# temperature_sensor.net
KiCad netlist of a schematic drawn in EAGLE
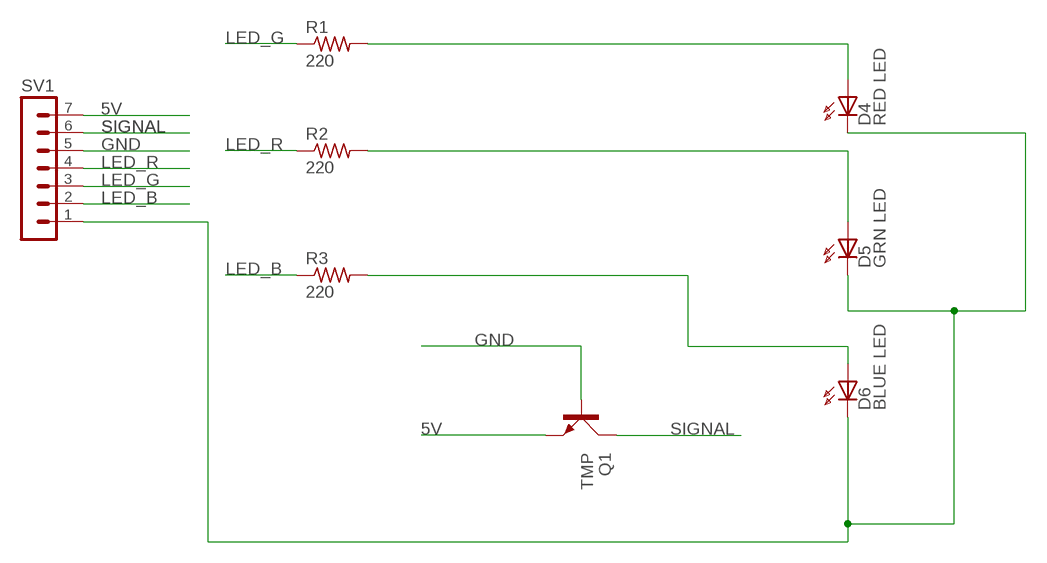
[diagram p0: schematic, sheet 1]

(export (version "E")
  (design (tool "Eeschema 10.0.6"))
  (components
    (comp (ref "D4")
      (value "RED LED")
      (footprint "eagle-import:HLMP6")
      (fields (field (name "MF") "AGILENT TECHNOLOGIES") (field (name "MPN") "HLMP-6500"))
      (libsource (lib "eagle-import") (part "HLMP6"))
    )
    (comp (ref "D5")
      (value "GRN LED")
      (footprint "eagle-import:HLMP6")
      (fields (field (name "MF") "AGILENT TECHNOLOGIES") (field (name "MPN") "HLMP-6500"))
      (libsource (lib "eagle-import") (part "HLMP6"))
    )
    (comp (ref "D6")
      (value "BLUE LED")
      (footprint "eagle-import:HLMP6")
      (fields (field (name "MF") "AGILENT TECHNOLOGIES") (field (name "MPN") "HLMP-6500"))
      (libsource (lib "eagle-import") (part "HLMP6"))
    )
    (comp (ref "Q1")
      (value "TMP")
      (footprint "eagle-import:TO126AV")
      (libsource (lib "eagle-import") (part "BD139"))
    )
    (comp (ref "R1")
      (value "220")
      (footprint "eagle-import:R1206")
      (libsource (lib "eagle-import") (part "R-US_R1206"))
    )
    (comp (ref "R2")
      (value "220")
      (footprint "eagle-import:R1206")
      (libsource (lib "eagle-import") (part "R-US_R1206"))
    )
    (comp (ref "R3")
      (value "220")
      (footprint "eagle-import:R1206")
      (libsource (lib "eagle-import") (part "R-US_R1206"))
    )
    (comp (ref "SV1")
      (value "MA07-1")
      (footprint "eagle-import:MA07-1")
      (libsource (lib "eagle-import") (part "MA07-1"))
    )
  )
  (nets
    (net (code "1") (name "/5V") (class "Default")
      (node (ref "Q1") (pin "E") (pinfunction "E_E") (pintype "passive"))
      (node (ref "SV1") (pin "7") (pinfunction "7_7") (pintype "passive"))
    )
    (net (code "2") (name "/GND") (class "Default")
      (node (ref "Q1") (pin "B") (pinfunction "B_B") (pintype "passive"))
      (node (ref "SV1") (pin "5") (pinfunction "5_5") (pintype "passive"))
    )
    (net (code "3") (name "/LED_B") (class "Default")
      (node (ref "R3") (pin "1") (pinfunction "1_1") (pintype "passive"))
      (node (ref "SV1") (pin "2") (pinfunction "2_2") (pintype "passive"))
    )
    (net (code "4") (name "/LED_G") (class "Default")
      (node (ref "R1") (pin "1") (pinfunction "1_1") (pintype "passive"))
      (node (ref "SV1") (pin "3") (pinfunction "3_3") (pintype "passive"))
    )
    (net (code "5") (name "/LED_R") (class "Default")
      (node (ref "R2") (pin "1") (pinfunction "1_1") (pintype "passive"))
      (node (ref "SV1") (pin "4") (pinfunction "4_4") (pintype "passive"))
    )
    (net (code "6") (name "/SIGNAL") (class "Default")
      (node (ref "Q1") (pin "C") (pinfunction "C_C") (pintype "passive"))
      (node (ref "SV1") (pin "6") (pinfunction "6_6") (pintype "passive"))
    )
    (net (code "7") (name "Net-(D4-PadA)") (class "Default")
      (node (ref "D4") (pin "A") (pinfunction "A_A") (pintype "passive"))
      (node (ref "R1") (pin "2") (pinfunction "2_2") (pintype "passive"))
    )
    (net (code "8") (name "Net-(D4-PadK)") (class "Default")
      (node (ref "D4") (pin "K") (pinfunction "K_K") (pintype "passive"))
      (node (ref "D5") (pin "K") (pinfunction "K_K") (pintype "passive"))
      (node (ref "D6") (pin "K") (pinfunction "K_K") (pintype "passive"))
      (node (ref "SV1") (pin "1") (pinfunction "1_1") (pintype "passive"))
    )
    (net (code "9") (name "Net-(D5-PadA)") (class "Default")
      (node (ref "D5") (pin "A") (pinfunction "A_A") (pintype "passive"))
      (node (ref "R2") (pin "2") (pinfunction "2_2") (pintype "passive"))
    )
    (net (code "10") (name "Net-(D6-PadA)") (class "Default")
      (node (ref "D6") (pin "A") (pinfunction "A_A") (pintype "passive"))
      (node (ref "R3") (pin "2") (pinfunction "2_2") (pintype "passive"))
    )
  )
)
